# PSU_DAQ_MCU.net
KiCad netlist of a schematic drawn in Altium Designer
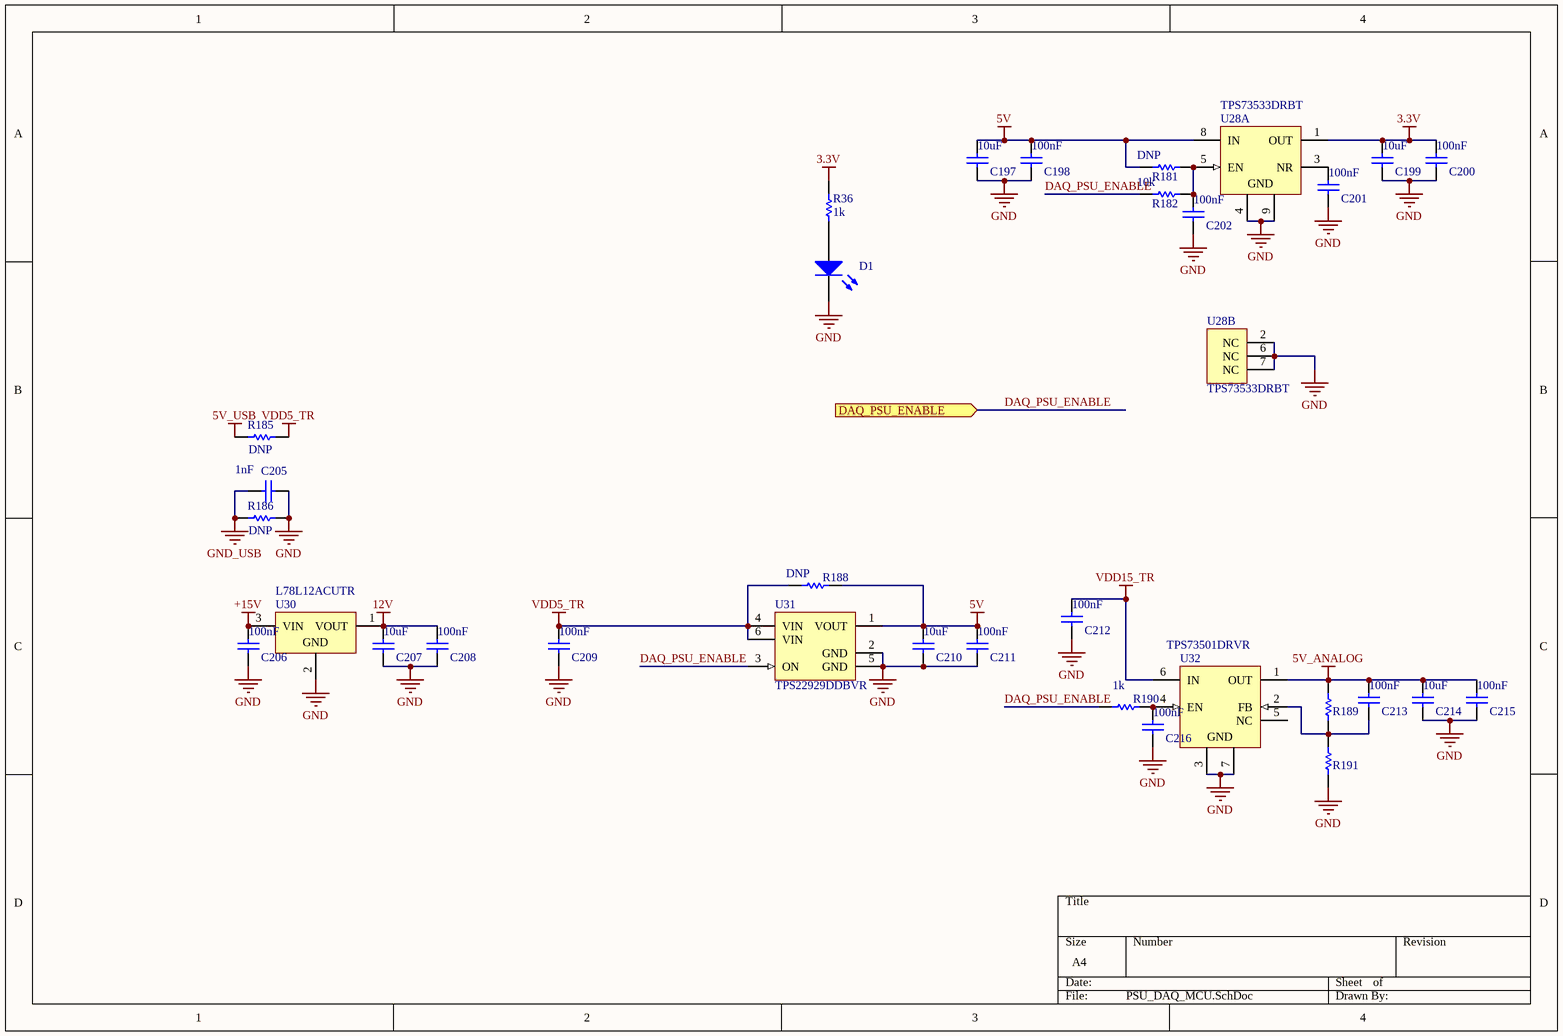
[diagram p0: PSU_DAQ_MCU.SchDoc]

(export (version "E")
  (design (tool "Eeschema 10.0.6"))
  (components
    (comp (ref "C197")
      (value "10uF")
      (footprint "CAPC0805(2012)145_L")
      (description "0805 (2012 Metric) Chip Capacitor")
      (fields (field (name "Comment") "CAP0805"))
      (libsource (lib "Altium Content Vault") (part "CMP-1590-00003-1"))
    )
    (comp (ref "C198")
      (value "100nF")
      (footprint "CAPC0402(1005)60_L")
      (description "0402 (1005 Metric) Chip Capacitor")
      (fields (field (name "Comment") "CAP0402"))
      (libsource (lib "Altium Content Vault") (part "CMP-1590-00004-1"))
    )
    (comp (ref "C199")
      (value "10uF")
      (footprint "CAPC0805(2012)145_L")
      (description "0805 (2012 Metric) Chip Capacitor")
      (fields (field (name "Comment") "CAP0805"))
      (libsource (lib "Altium Content Vault") (part "CMP-1590-00003-1"))
    )
    (comp (ref "C200")
      (value "100nF")
      (footprint "CAPC0402(1005)60_L")
      (description "0402 (1005 Metric) Chip Capacitor")
      (fields (field (name "Comment") "CAP0402"))
      (libsource (lib "Altium Content Vault") (part "CMP-1590-00004-1"))
    )
    (comp (ref "C201")
      (value "100nF")
      (footprint "CAPC0402(1005)60_L")
      (description "0402 (1005 Metric) Chip Capacitor")
      (fields (field (name "Comment") "CAP0402"))
      (libsource (lib "Altium Content Vault") (part "CMP-1590-00004-1"))
    )
    (comp (ref "C202")
      (value "100nF")
      (footprint "CAPC0402(1005)60_L")
      (description "0402 (1005 Metric) Chip Capacitor")
      (fields (field (name "Comment") "CAP0402"))
      (libsource (lib "Altium Content Vault") (part "CMP-1590-00004-1"))
    )
    (comp (ref "C205")
      (value "1nF")
      (footprint "CAPC1808(4520)175_L")
      (description "1808 (4520 Metric) Chip Capacitor")
      (fields (field (name "Comment") "CAP1808"))
      (libsource (lib "Altium Content Vault") (part "CMP-1590-00006-1"))
    )
    (comp (ref "C206")
      (value "100nF")
      (footprint "CAPC0402(1005)60_L")
      (description "0402 (1005 Metric) Chip Capacitor")
      (fields (field (name "Comment") "CAP0402"))
      (libsource (lib "Altium Content Vault") (part "CMP-1590-00004-1"))
    )
    (comp (ref "C207")
      (value "10uF")
      (footprint "CAPC0805(2012)145_L")
      (description "0805 (2012 Metric) Chip Capacitor")
      (fields (field (name "Comment") "CAP0805"))
      (libsource (lib "Altium Content Vault") (part "CMP-1590-00003-1"))
    )
    (comp (ref "C208")
      (value "100nF")
      (footprint "CAPC0402(1005)60_L")
      (description "0402 (1005 Metric) Chip Capacitor")
      (fields (field (name "Comment") "CAP0402"))
      (libsource (lib "Altium Content Vault") (part "CMP-1590-00004-1"))
    )
    (comp (ref "C209")
      (value "100nF")
      (footprint "CAPC0402(1005)60_L")
      (description "0402 (1005 Metric) Chip Capacitor")
      (fields (field (name "Comment") "CAP0402"))
      (libsource (lib "Altium Content Vault") (part "CMP-1590-00004-1"))
    )
    (comp (ref "C210")
      (value "10uF")
      (footprint "CAPC0805(2012)145_L")
      (description "0805 (2012 Metric) Chip Capacitor")
      (fields (field (name "Comment") "CAP0805"))
      (libsource (lib "Altium Content Vault") (part "CMP-1590-00003-1"))
    )
    (comp (ref "C211")
      (value "100nF")
      (footprint "CAPC0402(1005)60_L")
      (description "0402 (1005 Metric) Chip Capacitor")
      (fields (field (name "Comment") "CAP0402"))
      (libsource (lib "Altium Content Vault") (part "CMP-1590-00004-1"))
    )
    (comp (ref "C212")
      (value "100nF")
      (footprint "CAPC0402(1005)60_L")
      (description "0402 (1005 Metric) Chip Capacitor")
      (fields (field (name "Comment") "CAP0402"))
      (libsource (lib "Altium Content Vault") (part "CMP-1590-00004-1"))
    )
    (comp (ref "C213")
      (value "100nF")
      (footprint "CAPC0402(1005)60_L")
      (description "0402 (1005 Metric) Chip Capacitor")
      (fields (field (name "Comment") "CAP0402"))
      (libsource (lib "Altium Content Vault") (part "CMP-1590-00004-1"))
    )
    (comp (ref "C214")
      (value "10uF")
      (footprint "CAPC0805(2012)145_L")
      (description "0805 (2012 Metric) Chip Capacitor")
      (fields (field (name "Comment") "CAP0805"))
      (libsource (lib "Altium Content Vault") (part "CMP-1590-00003-1"))
    )
    (comp (ref "C215")
      (value "100nF")
      (footprint "CAPC0402(1005)60_L")
      (description "0402 (1005 Metric) Chip Capacitor")
      (fields (field (name "Comment") "CAP0402"))
      (libsource (lib "Altium Content Vault") (part "CMP-1590-00004-1"))
    )
    (comp (ref "C216")
      (value "100nF")
      (footprint "CAPC0402(1005)60_L")
      (description "0402 (1005 Metric) Chip Capacitor")
      (fields (field (name "Comment") "CAP0402"))
      (libsource (lib "Altium Content Vault") (part "CMP-1590-00004-1"))
    )
    (comp (ref "D1")
      (value "Green_LED_150060GS75000")
      (footprint "Green_LED_150060GS75000")
      (description "WURTH ELEKTRONIK  150060GS75000  LED, Green, SMD, 30 mA, 3.2 V, 520 nm")
      (fields
        (field (name "MANUFACTURER PART NUMBER") "150060GS75000")
        (field (name "MANUFACTURER") "WURTH ELEKTRONIK")
      )
      (libsource (lib "Kilian_UCC_Library") (part "Green_LED_150060GS75000"))
    )
    (comp (ref "R36")
      (value "1k")
      (footprint "RESC0402(1005)_L")
      (description "0402 (1005 Metric) Chip Resistor")
      (fields (field (name "Comment") "RES0402"))
      (libsource (lib "Altium Content Vault") (part "CMP-1591-00004-1"))
    )
    (comp (ref "R181")
      (value "DNP")
      (footprint "RESC0402(1005)_L")
      (description "0402 (1005 Metric) Chip Resistor")
      (fields (field (name "Comment") "RES0402"))
      (libsource (lib "Altium Content Vault") (part "CMP-1591-00004-1"))
    )
    (comp (ref "R182")
      (value "10k")
      (footprint "RESC0402(1005)_L")
      (description "0402 (1005 Metric) Chip Resistor")
      (fields (field (name "Comment") "RES0402"))
      (libsource (lib "Altium Content Vault") (part "CMP-1591-00004-1"))
    )
    (comp (ref "R185")
      (value "DNP")
      (footprint "RESC2010(5025)_L")
      (description "2010 (5025 Metric) Chip Resistor")
      (fields (field (name "Comment") "RES2010"))
      (libsource (lib "Altium Content Vault") (part "CMP-1591-00006-1"))
    )
    (comp (ref "R186")
      (value "DNP")
      (footprint "RESC2010(5025)_L")
      (description "2010 (5025 Metric) Chip Resistor")
      (fields (field (name "Comment") "RES2010"))
      (libsource (lib "Altium Content Vault") (part "CMP-1591-00006-1"))
    )
    (comp (ref "R188")
      (value "DNP")
      (footprint "RESC0402(1005)_L")
      (description "0402 (1005 Metric) Chip Resistor")
      (fields (field (name "Comment") "RES0402"))
      (libsource (lib "Altium Content Vault") (part "CMP-1591-00004-1"))
    )
    (comp (ref "R189")
      (value "RES0402")
      (footprint "RESC0402(1005)_L")
      (description "0402 (1005 Metric) Chip Resistor")
      (libsource (lib "Altium Content Vault") (part "RES_3"))
    )
    (comp (ref "R190")
      (value "1k")
      (footprint "RESC0402(1005)_L")
      (description "0402 (1005 Metric) Chip Resistor")
      (fields (field (name "Comment") "RES0402"))
      (libsource (lib "Altium Content Vault") (part "CMP-1591-00004-1"))
    )
    (comp (ref "R191")
      (value "RES0402")
      (footprint "RESC0402(1005)_L")
      (description "0402 (1005 Metric) Chip Resistor")
      (libsource (lib "Altium Content Vault") (part "RES_3"))
    )
    (comp (ref "U28")
      (value "TPS73533DRBT")
      (footprint "DRB0008A_V")
      (fields (field (name "MANUFACTURER") "Texas Instruments"))
      (libsource (lib "Altium Content Vault") (part "TI-TPS735XXDRB8-1750X1500TP"))
    )
    (comp (ref "U30")
      (value "L78L12ACUTR")
      (footprint "SOT-89_N")
      (description "Positive Voltage Regulator, 12V, 4-Pin SOT-89, Tape and Reel")
      (libsource (lib "Altium Content Vault") (part "PM-REG-7805-SIL3"))
    )
    (comp (ref "U31")
      (value "TPS22929DDBVR")
      (footprint "DBV6_N")
      (fields (field (name "MANUFACTURER") "Texas Instruments"))
      (libsource (lib "Altium Content Vault") (part "TI-TPS22929DDBV6"))
    )
    (comp (ref "U32")
      (value "TPS73501DRVR")
      (footprint "TI-DRV6-1600X1000TP_V")
      (fields (field (name "MANUFACTURER") "Texas Instruments"))
      (libsource (lib "Altium Content Vault") (part "TI-TPS7XXXXDRV6-1600X1000TP"))
    )
  )
  (nets
    (net (code "1") (name "+15V") (class "Default")
      (node (ref "C206") (pin "1") (pinfunction "1_1") (pintype "passive"))
      (node (ref "U30") (pin "3") (pinfunction "VIN_3") (pintype "power_in"))
    )
    (net (code "2") (name "/DAQ_PSU_ENABLE") (class "Default")
      (node (ref "R182") (pin "1") (pinfunction "1_1") (pintype "passive"))
      (node (ref "R190") (pin "2") (pinfunction "2_2") (pintype "passive"))
      (node (ref "U31") (pin "3") (pinfunction "ON_3") (pintype "input"))
    )
    (net (code "3") (name "3.3V") (class "Default")
      (node (ref "C199") (pin "2") (pinfunction "2_2") (pintype "passive"))
      (node (ref "C200") (pin "1") (pinfunction "1_1") (pintype "passive"))
      (node (ref "R36") (pin "1") (pinfunction "1_1") (pintype "passive"))
      (node (ref "U28") (pin "1") (pinfunction "OUT_1") (pintype "power_in"))
    )
    (net (code "4") (name "5V") (class "Default")
      (node (ref "C197") (pin "2") (pinfunction "2_2") (pintype "passive"))
      (node (ref "C198") (pin "1") (pinfunction "1_1") (pintype "passive"))
      (node (ref "C210") (pin "2") (pinfunction "2_2") (pintype "passive"))
      (node (ref "C211") (pin "1") (pinfunction "1_1") (pintype "passive"))
      (node (ref "R181") (pin "1") (pinfunction "1_1") (pintype "passive"))
      (node (ref "R188") (pin "1") (pinfunction "1_1") (pintype "passive"))
      (node (ref "U28") (pin "8") (pinfunction "IN_8") (pintype "power_in"))
      (node (ref "U31") (pin "1") (pinfunction "VOUT_1") (pintype "power_in"))
    )
    (net (code "5") (name "5V_ANALOG") (class "Default")
      (node (ref "C213") (pin "1") (pinfunction "1_1") (pintype "passive"))
      (node (ref "C214") (pin "2") (pinfunction "2_2") (pintype "passive"))
      (node (ref "C215") (pin "1") (pinfunction "1_1") (pintype "passive"))
      (node (ref "R189") (pin "1") (pinfunction "1_1") (pintype "passive"))
      (node (ref "U32") (pin "1") (pinfunction "OUT_1") (pintype "power_in"))
    )
    (net (code "6") (name "5V_USB") (class "Default")
      (node (ref "R185") (pin "1") (pinfunction "1_1") (pintype "passive"))
    )
    (net (code "7") (name "12V") (class "Default")
      (node (ref "C207") (pin "2") (pinfunction "2_2") (pintype "passive"))
      (node (ref "C208") (pin "1") (pinfunction "1_1") (pintype "passive"))
      (node (ref "U30") (pin "1") (pinfunction "VOUT_1") (pintype "power_in"))
    )
    (net (code "8") (name "GND") (class "Default")
      (node (ref "C197") (pin "1") (pinfunction "1_1") (pintype "passive"))
      (node (ref "C198") (pin "2") (pinfunction "2_2") (pintype "passive"))
      (node (ref "C199") (pin "1") (pinfunction "1_1") (pintype "passive"))
      (node (ref "C200") (pin "2") (pinfunction "2_2") (pintype "passive"))
      (node (ref "C201") (pin "2") (pinfunction "2_2") (pintype "passive"))
      (node (ref "C202") (pin "2") (pinfunction "2_2") (pintype "passive"))
      (node (ref "C205") (pin "2") (pinfunction "2_2") (pintype "passive"))
      (node (ref "C206") (pin "2") (pinfunction "2_2") (pintype "passive"))
      (node (ref "C207") (pin "1") (pinfunction "1_1") (pintype "passive"))
      (node (ref "C208") (pin "2") (pinfunction "2_2") (pintype "passive"))
      (node (ref "C209") (pin "2") (pinfunction "2_2") (pintype "passive"))
      (node (ref "C210") (pin "1") (pinfunction "1_1") (pintype "passive"))
      (node (ref "C211") (pin "2") (pinfunction "2_2") (pintype "passive"))
      (node (ref "C212") (pin "2") (pinfunction "2_2") (pintype "passive"))
      (node (ref "C214") (pin "1") (pinfunction "1_1") (pintype "passive"))
      (node (ref "C215") (pin "2") (pinfunction "2_2") (pintype "passive"))
      (node (ref "C216") (pin "2") (pinfunction "2_2") (pintype "passive"))
      (node (ref "D1") (pin "1") (pinfunction "1_1") (pintype "passive"))
      (node (ref "R186") (pin "2") (pinfunction "2_2") (pintype "passive"))
      (node (ref "R191") (pin "2") (pinfunction "2_2") (pintype "passive"))
      (node (ref "U28") (pin "2") (pinfunction "NC_2") (pintype "passive"))
      (node (ref "U28") (pin "4") (pinfunction "GND_4") (pintype "power_in"))
      (node (ref "U28") (pin "6") (pinfunction "NC_6") (pintype "passive"))
      (node (ref "U28") (pin "7") (pinfunction "NC_7") (pintype "passive"))
      (node (ref "U28") (pin "9") (pinfunction "GND_9") (pintype "power_in"))
      (node (ref "U30") (pin "2") (pinfunction "GND_2") (pintype "power_in"))
      (node (ref "U31") (pin "2") (pinfunction "GND_2") (pintype "power_in"))
      (node (ref "U31") (pin "5") (pinfunction "GND_5") (pintype "power_in"))
      (node (ref "U32") (pin "3") (pinfunction "GND_3") (pintype "power_in"))
      (node (ref "U32") (pin "7") (pinfunction "GND_7") (pintype "power_in"))
    )
    (net (code "9") (name "GND_USB") (class "Default")
      (node (ref "C205") (pin "1") (pinfunction "1_1") (pintype "passive"))
      (node (ref "R186") (pin "1") (pinfunction "1_1") (pintype "passive"))
    )
    (net (code "10") (name "Net-(D1-Pad2)") (class "Default")
      (node (ref "D1") (pin "2") (pinfunction "2_2") (pintype "passive"))
      (node (ref "R36") (pin "2") (pinfunction "2_2") (pintype "passive"))
    )
    (net (code "11") (name "Net-(U28A-EN)") (class "Default")
      (node (ref "C202") (pin "1") (pinfunction "1_1") (pintype "passive"))
      (node (ref "R181") (pin "2") (pinfunction "2_2") (pintype "passive"))
      (node (ref "R182") (pin "2") (pinfunction "2_2") (pintype "passive"))
      (node (ref "U28") (pin "5") (pinfunction "EN_5") (pintype "input"))
    )
    (net (code "12") (name "Net-(U28A-NR)") (class "Default")
      (node (ref "C201") (pin "1") (pinfunction "1_1") (pintype "passive"))
      (node (ref "U28") (pin "3") (pinfunction "NR_3") (pintype "passive"))
    )
    (net (code "13") (name "Net-(U32-EN)") (class "Default")
      (node (ref "C216") (pin "1") (pinfunction "1_1") (pintype "passive"))
      (node (ref "R190") (pin "1") (pinfunction "1_1") (pintype "passive"))
      (node (ref "U32") (pin "4") (pinfunction "EN_4") (pintype "input"))
    )
    (net (code "14") (name "Net-(U32-FB)") (class "Default")
      (node (ref "C213") (pin "2") (pinfunction "2_2") (pintype "passive"))
      (node (ref "R189") (pin "2") (pinfunction "2_2") (pintype "passive"))
      (node (ref "R191") (pin "1") (pinfunction "1_1") (pintype "passive"))
      (node (ref "U32") (pin "2") (pinfunction "FB_2") (pintype "input"))
    )
    (net (code "15") (name "VDD5_TR") (class "Default")
      (node (ref "C209") (pin "1") (pinfunction "1_1") (pintype "passive"))
      (node (ref "R185") (pin "2") (pinfunction "2_2") (pintype "passive"))
      (node (ref "R188") (pin "2") (pinfunction "2_2") (pintype "passive"))
      (node (ref "U31") (pin "4") (pinfunction "VIN_4") (pintype "power_in"))
      (node (ref "U31") (pin "6") (pinfunction "VIN_6") (pintype "power_in"))
    )
    (net (code "16") (name "VDD15_TR") (class "Default")
      (node (ref "C212") (pin "1") (pinfunction "1_1") (pintype "passive"))
      (node (ref "U32") (pin "6") (pinfunction "IN_6") (pintype "power_in"))
    )
    (net (code "17") (name "unconnected-(U32-NC-Pad5)") (class "Default")
      (node (ref "U32") (pin "5") (pinfunction "NC_5") (pintype "passive"))
    )
  )
)
